# NewPSU.net
KiCad netlist of a schematic drawn in Altium Designer
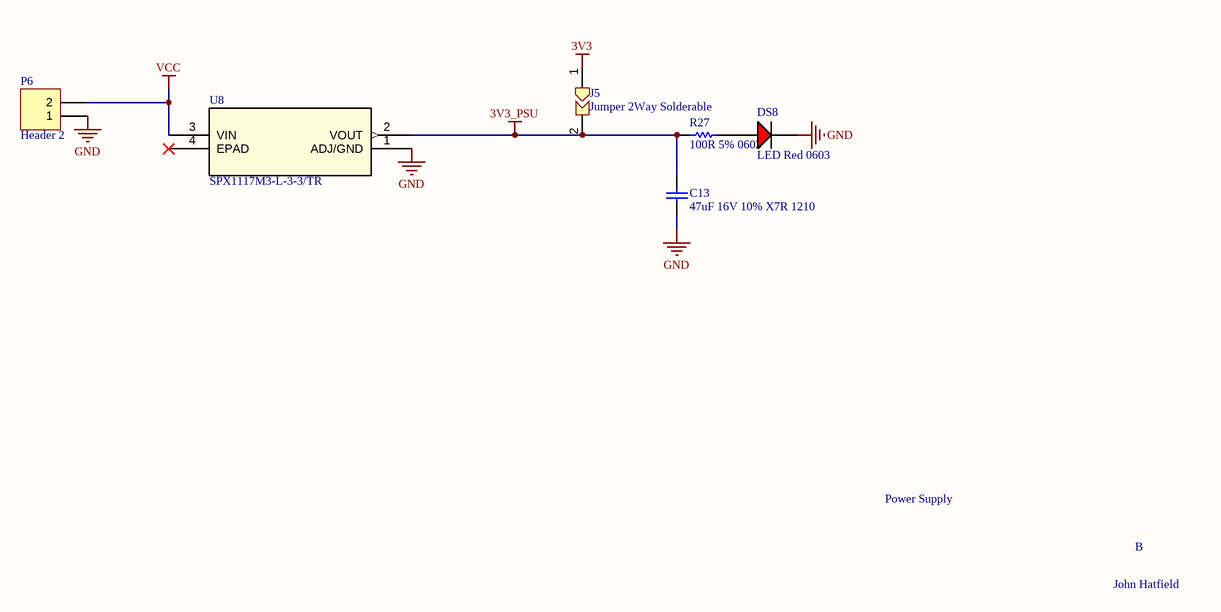
[diagram p0: NewPSU.SchDoc]

(export (version "E")
  (design (tool "Eeschema 10.0.6"))
  (components
    (comp (ref "C13")
      (value "47uF 16V 10% X7R 1210")
      (footprint "Cap_Ceramic_1210")
      (description "Capacitor, Ceramic, SMD, 47uF, 16V, 5%, X7R, 1210")
      (libsource (lib "StandardCapacitors") (part "47uF 16V 10% X7R 1210"))
    )
    (comp (ref "DS8")
      (value "LED Red 0603")
      (footprint "LED RED 0603")
      (libsource (lib "QUTMS_LEDLibrary") (part "LED Red 0603"))
    )
    (comp (ref "J5")
      (value "Jumper 2Way Solderable")
      (footprint "Jumper_2Way_Solderable")
      (description "Jumper 2Way Vert Solderable")
      (libsource (lib "QUTMS_JumperLibrary") (part "Jumper 2Way Vert Solderable"))
    )
    (comp (ref "P6")
      (value "Header 2")
      (footprint "HDR1X2")
      (description "Header, 2-Pin")
      (fields (field (name "PUBLISHER") "Altium Limited"))
      (libsource (lib "Miscellaneous Connectors") (part "Header 2"))
    )
    (comp (ref "R27")
      (value "100R 5% 0603")
      (footprint "Res_ThinFilm_0603")
      (description "Resistor, SMD, 100R, 0.1W, 5%, 0603")
      (libsource (lib "StandardResistors") (part "100R 5%, 0603"))
    )
    (comp (ref "U8")
      (value "SPX1117M3-L-3-3/TR")
      (footprint "SOT223-3_MXL")
      (description "No Description Available")
      (fields (field (name "COPYRIGHT") "Copyright (C) 2018 Accelerated Designs. All rights reserved"))
      (libsource (lib "2021-04-19_10-34-43") (part "SPX1117M3-L-3-3/TR"))
    )
  )
  (nets
    (net (code "1") (name "3V3") (class "Default")
      (node (ref "J5") (pin "1") (pinfunction "1_1") (pintype "passive"))
    )
    (net (code "2") (name "3V3_PSU") (class "Default")
      (node (ref "C13") (pin "2") (pinfunction "2_2") (pintype "passive"))
      (node (ref "J5") (pin "2") (pinfunction "2_2") (pintype "passive"))
      (node (ref "R27") (pin "1") (pinfunction "1_1") (pintype "passive"))
      (node (ref "U8") (pin "2") (pinfunction "VOUT_2") (pintype "output"))
    )
    (net (code "3") (name "GND") (class "Default")
      (node (ref "C13") (pin "1") (pinfunction "1_1") (pintype "passive"))
      (node (ref "DS8") (pin "2") (pinfunction "C_2") (pintype "passive"))
      (node (ref "P6") (pin "1") (pinfunction "1_1") (pintype "passive"))
      (node (ref "U8") (pin "1") (pinfunction "ADJ/GND_1") (pintype "passive"))
    )
    (net (code "4") (name "Net-(DS8-A)") (class "Default")
      (node (ref "DS8") (pin "1") (pinfunction "A_1") (pintype "passive"))
      (node (ref "R27") (pin "2") (pinfunction "2_2") (pintype "passive"))
    )
    (net (code "5") (name "VCC") (class "Default")
      (node (ref "P6") (pin "2") (pinfunction "2_2") (pintype "passive"))
      (node (ref "U8") (pin "3") (pinfunction "VIN_3") (pintype "passive"))
    )
    (net (code "6") (name "unconnected-(U8-EPAD-Pad4)") (class "Default")
      (node (ref "U8") (pin "4") (pinfunction "EPAD_4") (pintype "passive+no_connect"))
    )
  )
)
